# TI_TPS56837.net
KiCad netlist of a schematic drawn in Altium Designer
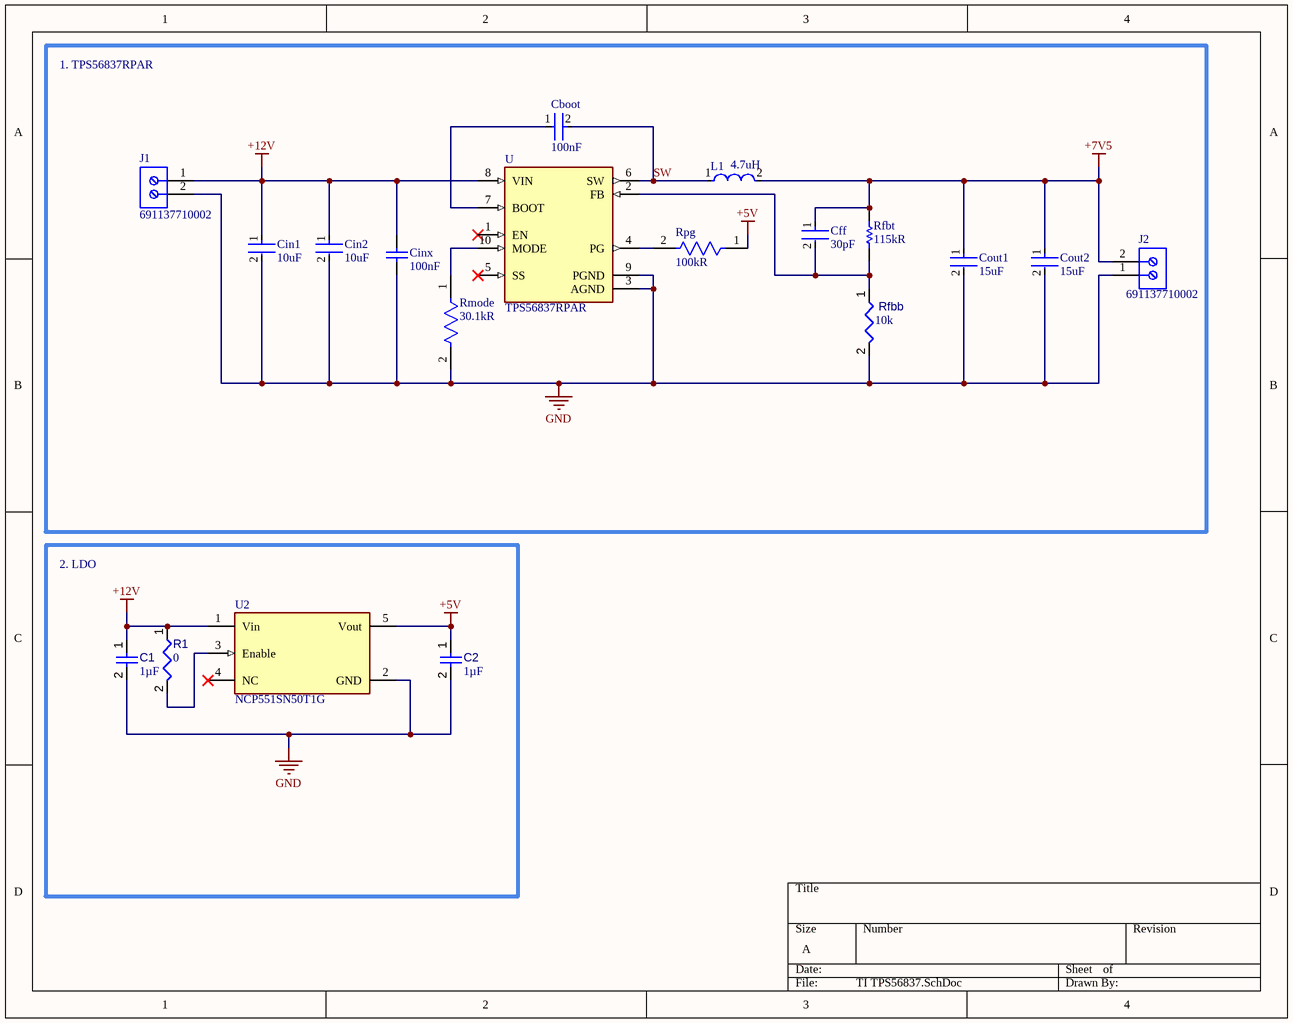
[diagram p0: TI TPS56837.SchDoc]

(export (version "E")
  (design (tool "Eeschema 10.0.6"))
  (components
    (comp (ref "C1")
      (value "1µF")
      (footprint "CAPC0402(1005)60_L")
      (description "Chip Capacitor, 1µF +/-20%, 10V, 0402, Thickness 0.6 mm")
      (fields (field (name "TOLERANCE") "10%") (field (name "Comment") "Capacitor 1µF +/-20% 10V 0402"))
      (libsource (lib "SUBC") (part "CAP-NP-2"))
    )
    (comp (ref "C2")
      (value "1µF")
      (footprint "CAPC0402(1005)60_L")
      (description "Chip Capacitor, 1µF +/-20%, 10V, 0402, Thickness 0.6 mm")
      (fields (field (name "TOLERANCE") "10%") (field (name "Comment") "Capacitor 1µF +/-20% 10V 0402"))
      (libsource (lib "SUBC") (part "CAP-NP-2"))
    )
    (comp (ref "Cboot")
      (value "100nF")
      (footprint "FP-GRM15-MFG")
      (description "Multilayer Ceramic Capacitor, 0.1 uF, 16 V, ± 10%, X7R, 0402 [1005 Metric]")
      (fields (field (name "VOLTAGE") "16V") (field (name "TOLERANCE") "10%"))
      (libsource (lib "SUBC") (part "236180d848d6139a670b325ea6854c9"))
    )
    (comp (ref "Cff")
      (value "30pF")
      (footprint "FP-CL10-IPC_B")
      (description "Cap Ceramic 30pF 50V C0G 1% SMD 0603 125°C Paper T/R")
      (fields (field (name "TOLERANCE") "1%") (field (name "Comment") "CL10C300FB8NNNC"))
      (libsource (lib "SUBC") (part "b4654b650e69147ec39a6b967a45e02"))
    )
    (comp (ref "Cin1")
      (value "10uF")
      (footprint "FP-GRM21B-0_15-IPC_A")
      (description "Multilayer Ceramic Capacitor, 10 uF, 25 V, ± 20%, X5R, 0805 [2012 Metric]")
      (fields (field (name "TOLERANCE") "20%") (field (name "Comment") "GRM21BR61E106MA73L"))
      (libsource (lib "SUBC") (part "b4654b650e69147ec39a6b967a45e02"))
    )
    (comp (ref "Cin2")
      (value "10uF")
      (footprint "FP-GRM21B-0_15-IPC_A")
      (description "Multilayer Ceramic Capacitor, 10 uF, 25 V, ± 20%, X5R, 0805 [2012 Metric]")
      (fields (field (name "TOLERANCE") "20%") (field (name "Comment") "GRM21BR61E106MA73L"))
      (libsource (lib "SUBC") (part "b4654b650e69147ec39a6b967a45e02"))
    )
    (comp (ref "Cinx")
      (value "100nF")
      (footprint "CAPC2013X135X45LL10T25")
      (description "CAP CER 0.1UF 50V X7R 0805 / Cap Ceramic 0.1uF 50V X7R 10% Pad SMD 0805 125°C T/R")
      (fields (field (name "TOLERANCE") "10%") (field (name "VOLTAGE") "50V"))
      (libsource (lib "") (part "CAP-NP-2_1"))
    )
    (comp (ref "Cout1")
      (value "15uF")
      (footprint "FP-C3225-250-0_4-IPC_A")
      (fields (field (name "TOLERANCE") "20%") (field (name "Comment") "C3225X5R1C156M250AA"))
      (libsource (lib "SUBC") (part "02cd4be3c70576c341d710602a673aa"))
    )
    (comp (ref "Cout2")
      (value "15uF")
      (footprint "FP-C3225-250-0_4-IPC_A")
      (fields (field (name "TOLERANCE") "20%") (field (name "Comment") "C3225X5R1C156M250AA"))
      (libsource (lib "SUBC") (part "02cd4be3c70576c341d710602a673aa"))
    )
    (comp (ref "J1")
      (value "691137710002")
      (footprint "691137710002")
      (description "Series 1377 - 5.00 mm Horizontal Entry with Pressure Clamp WR-TBL, 2 pin")
      (fields (field (name "VOLTAGE") "300V"))
      (libsource (lib "SUBC") (part "TBL - 1R - 02P - Screw"))
    )
    (comp (ref "J2")
      (value "691137710002")
      (footprint "691137710002")
      (description "Series 1377 - 5.00 mm Horizontal Entry with Pressure Clamp WR-TBL, 2 pin")
      (fields (field (name "VOLTAGE") "300V"))
      (libsource (lib "SUBC") (part "TBL - 1R - 02P - Screw"))
    )
    (comp (ref "L1")
      (value "4.7uH")
      (footprint "FP-IHLP-5050EZ-FP_3_226x4-MFG")
      (description "Inductor Power Shielded Wirewound 4.7uH 20% 100KHz Powdered Iron 12A 15mOhm DCR 5050 T/R")
      (fields (field (name "TOLERANCE") "20%") (field (name "Comment") "IHLP5050EZER4R7M01"))
      (libsource (lib "SUBC") (part "725321dda6339637d4d059423bc1c3c"))
    )
    (comp (ref "R1")
      (value "0")
      (footprint "RESC0402(1005)_L")
      (description "Jumper 0402 (1005 Metric)")
      (fields (field (name "Comment") "0R2J"))
      (libsource (lib "SUBC") (part "0R2J"))
    )
    (comp (ref "Rfbb")
      (value "10k")
      (footprint "RESC0402(1005)_L")
      (description "Chip Resistor, 10 kOhms, +/-1 %, 63 mW, -55 to 125 degC, 0402")
      (fields (field (name "POWER") "63mW") (field (name "TOLERANCE") "1%"))
      (libsource (lib "SUBC") (part "RES-2"))
    )
    (comp (ref "Rfbt")
      (value "115kR")
      (footprint "RESC2013X70X40NL20T20")
      (description "Res Thick Film 0805 115K Ohm 1% 0.125W ±100ppm/°C Molded SMD Punched Carrier T/R")
      (fields (field (name "TOLERANCE") "1%") (field (name "Comment") "ERJ-6ENF1153V"))
      (libsource (lib "SUBC") (part "RES"))
    )
    (comp (ref "Rmode")
      (value "30.1kR")
      (footprint "FP-CRCW0402-e3-IPC_A")
      (description "SMD Chip Resistor, 30.1 kOhm, ± 1%, 63 mW, 0402 [1005 Metric], Thick Film, General Purpose")
      (fields (field (name "TOLERANCE") "1%") (field (name "Comment") "CRCW040230K1FKED"))
      (libsource (lib "SUBC") (part "1029c3af85768c4190bb7ad29bc67b5"))
    )
    (comp (ref "Rpg")
      (value "100kR")
      (footprint "FP-CRCW0402-e3-IPC_A")
      (description "SMD Chip Resistor, 100 kOhm, ± 1%, 63 mW, 0402 [1005 Metric], Thick Film, General Purpose")
      (fields (field (name "TOLERANCE") "1%") (field (name "Comment") "CRCW0402100KFKED"))
      (libsource (lib "SUBC") (part "1029c3af85768c4190bb7ad29bc67b5"))
    )
    (comp (ref "U")
      (value "TPS56837RPAR")
      (footprint "CONV_TPS56637RPAR")
      (description "4.5-V to 28-V input, 8-A synchronous buck converter 10-VQFN-HR -40 to 150")
      (fields (field (name "MP") "TPS56637RPAR") (field (name "MF") "Texas Instruments"))
      (libsource (lib "SUBC") (part "TPS56637RPAR"))
    )
    (comp (ref "U2")
      (value "NCP551SN50T1G")
      (footprint "FP-483-IPC_C")
      (description "NCP551SN50T1G; LDO Voltage Regulator; 150mA; 5 V 2%; 0 to 12 Vin; 5-Pin TSOP")
      (libsource (lib "SUBC") (part "b78975ea1e21938e5c3db6828342147"))
    )
  )
  (nets
    (net (code "1") (name "+5V") (class "Default")
      (node (ref "C2") (pin "1") (pinfunction "1_1") (pintype "passive"))
      (node (ref "Rpg") (pin "1") (pinfunction "1_1") (pintype "passive"))
      (node (ref "U2") (pin "5") (pinfunction "Vout_5") (pintype "power_in"))
    )
    (net (code "2") (name "+7V5") (class "Default")
      (node (ref "Cff") (pin "1") (pinfunction "1_1") (pintype "passive"))
      (node (ref "Cout1") (pin "1") (pinfunction "1_1") (pintype "passive"))
      (node (ref "Cout2") (pin "1") (pinfunction "1_1") (pintype "passive"))
      (node (ref "J2") (pin "2") (pinfunction "2_2") (pintype "passive"))
      (node (ref "L1") (pin "2") (pinfunction "2_2") (pintype "passive"))
      (node (ref "Rfbt") (pin "1") (pinfunction "1_1") (pintype "passive"))
    )
    (net (code "3") (name "+12V") (class "Default")
      (node (ref "C1") (pin "1") (pinfunction "1_1") (pintype "passive"))
      (node (ref "Cin1") (pin "1") (pinfunction "1_1") (pintype "passive"))
      (node (ref "Cin2") (pin "1") (pinfunction "1_1") (pintype "passive"))
      (node (ref "Cinx") (pin "1") (pinfunction "1_1") (pintype "passive"))
      (node (ref "J1") (pin "1") (pinfunction "1_1") (pintype "passive"))
      (node (ref "R1") (pin "1") (pinfunction "1_1") (pintype "passive"))
      (node (ref "U") (pin "8") (pinfunction "VIN_8") (pintype "input"))
      (node (ref "U2") (pin "1") (pinfunction "Vin_1") (pintype "power_in"))
    )
    (net (code "4") (name "/SW") (class "Default")
      (node (ref "Cboot") (pin "2") (pinfunction "2_2") (pintype "passive"))
      (node (ref "L1") (pin "1") (pinfunction "1_1") (pintype "passive"))
      (node (ref "U") (pin "6") (pinfunction "SW_6") (pintype "output"))
    )
    (net (code "5") (name "GND") (class "Default")
      (node (ref "C1") (pin "2") (pinfunction "2_2") (pintype "passive"))
      (node (ref "C2") (pin "2") (pinfunction "2_2") (pintype "passive"))
      (node (ref "Cin1") (pin "2") (pinfunction "2_2") (pintype "passive"))
      (node (ref "Cin2") (pin "2") (pinfunction "2_2") (pintype "passive"))
      (node (ref "Cinx") (pin "2") (pinfunction "2_2") (pintype "passive"))
      (node (ref "Cout1") (pin "2") (pinfunction "2_2") (pintype "passive"))
      (node (ref "Cout2") (pin "2") (pinfunction "2_2") (pintype "passive"))
      (node (ref "J1") (pin "2") (pinfunction "2_2") (pintype "passive"))
      (node (ref "J2") (pin "1") (pinfunction "1_1") (pintype "passive"))
      (node (ref "Rfbb") (pin "2") (pinfunction "2_2") (pintype "passive"))
      (node (ref "Rmode") (pin "2") (pinfunction "2_2") (pintype "passive"))
      (node (ref "U") (pin "3") (pinfunction "AGND_3") (pintype "power_in"))
      (node (ref "U") (pin "9") (pinfunction "PGND_9") (pintype "power_in"))
      (node (ref "U2") (pin "2") (pinfunction "GND_2") (pintype "power_in"))
    )
    (net (code "6") (name "Net-(U-BOOT)") (class "Default")
      (node (ref "Cboot") (pin "1") (pinfunction "1_1") (pintype "passive"))
      (node (ref "U") (pin "7") (pinfunction "BOOT_7") (pintype "input"))
    )
    (net (code "7") (name "Net-(U-FB)") (class "Default")
      (node (ref "Cff") (pin "2") (pinfunction "2_2") (pintype "passive"))
      (node (ref "Rfbb") (pin "1") (pinfunction "1_1") (pintype "passive"))
      (node (ref "Rfbt") (pin "2") (pinfunction "2_2") (pintype "passive"))
      (node (ref "U") (pin "2") (pinfunction "FB_2") (pintype "input"))
    )
    (net (code "8") (name "Net-(U-MODE)") (class "Default")
      (node (ref "Rmode") (pin "1") (pinfunction "1_1") (pintype "passive"))
      (node (ref "U") (pin "10") (pinfunction "MODE_10") (pintype "input"))
    )
    (net (code "9") (name "Net-(U-PG)") (class "Default")
      (node (ref "Rpg") (pin "2") (pinfunction "2_2") (pintype "passive"))
      (node (ref "U") (pin "4") (pinfunction "PG_4") (pintype "output"))
    )
    (net (code "10") (name "Net-(U2-Enable)") (class "Default")
      (node (ref "R1") (pin "2") (pinfunction "2_2") (pintype "passive"))
      (node (ref "U2") (pin "3") (pinfunction "Enable_3") (pintype "input"))
    )
    (net (code "11") (name "unconnected-(U-EN-Pad1)") (class "Default")
      (node (ref "U") (pin "1") (pinfunction "EN_1") (pintype "input+no_connect"))
    )
    (net (code "12") (name "unconnected-(U-SS-Pad5)") (class "Default")
      (node (ref "U") (pin "5") (pinfunction "SS_5") (pintype "input+no_connect"))
    )
    (net (code "13") (name "unconnected-(U2-NC-Pad4)") (class "Default")
      (node (ref "U2") (pin "4") (pinfunction "NC_4") (pintype "passive+no_connect"))
    )
  )
)
